# Nixie_Clock_Power_Supply.net
KiCad netlist of a schematic drawn in EasyEDA
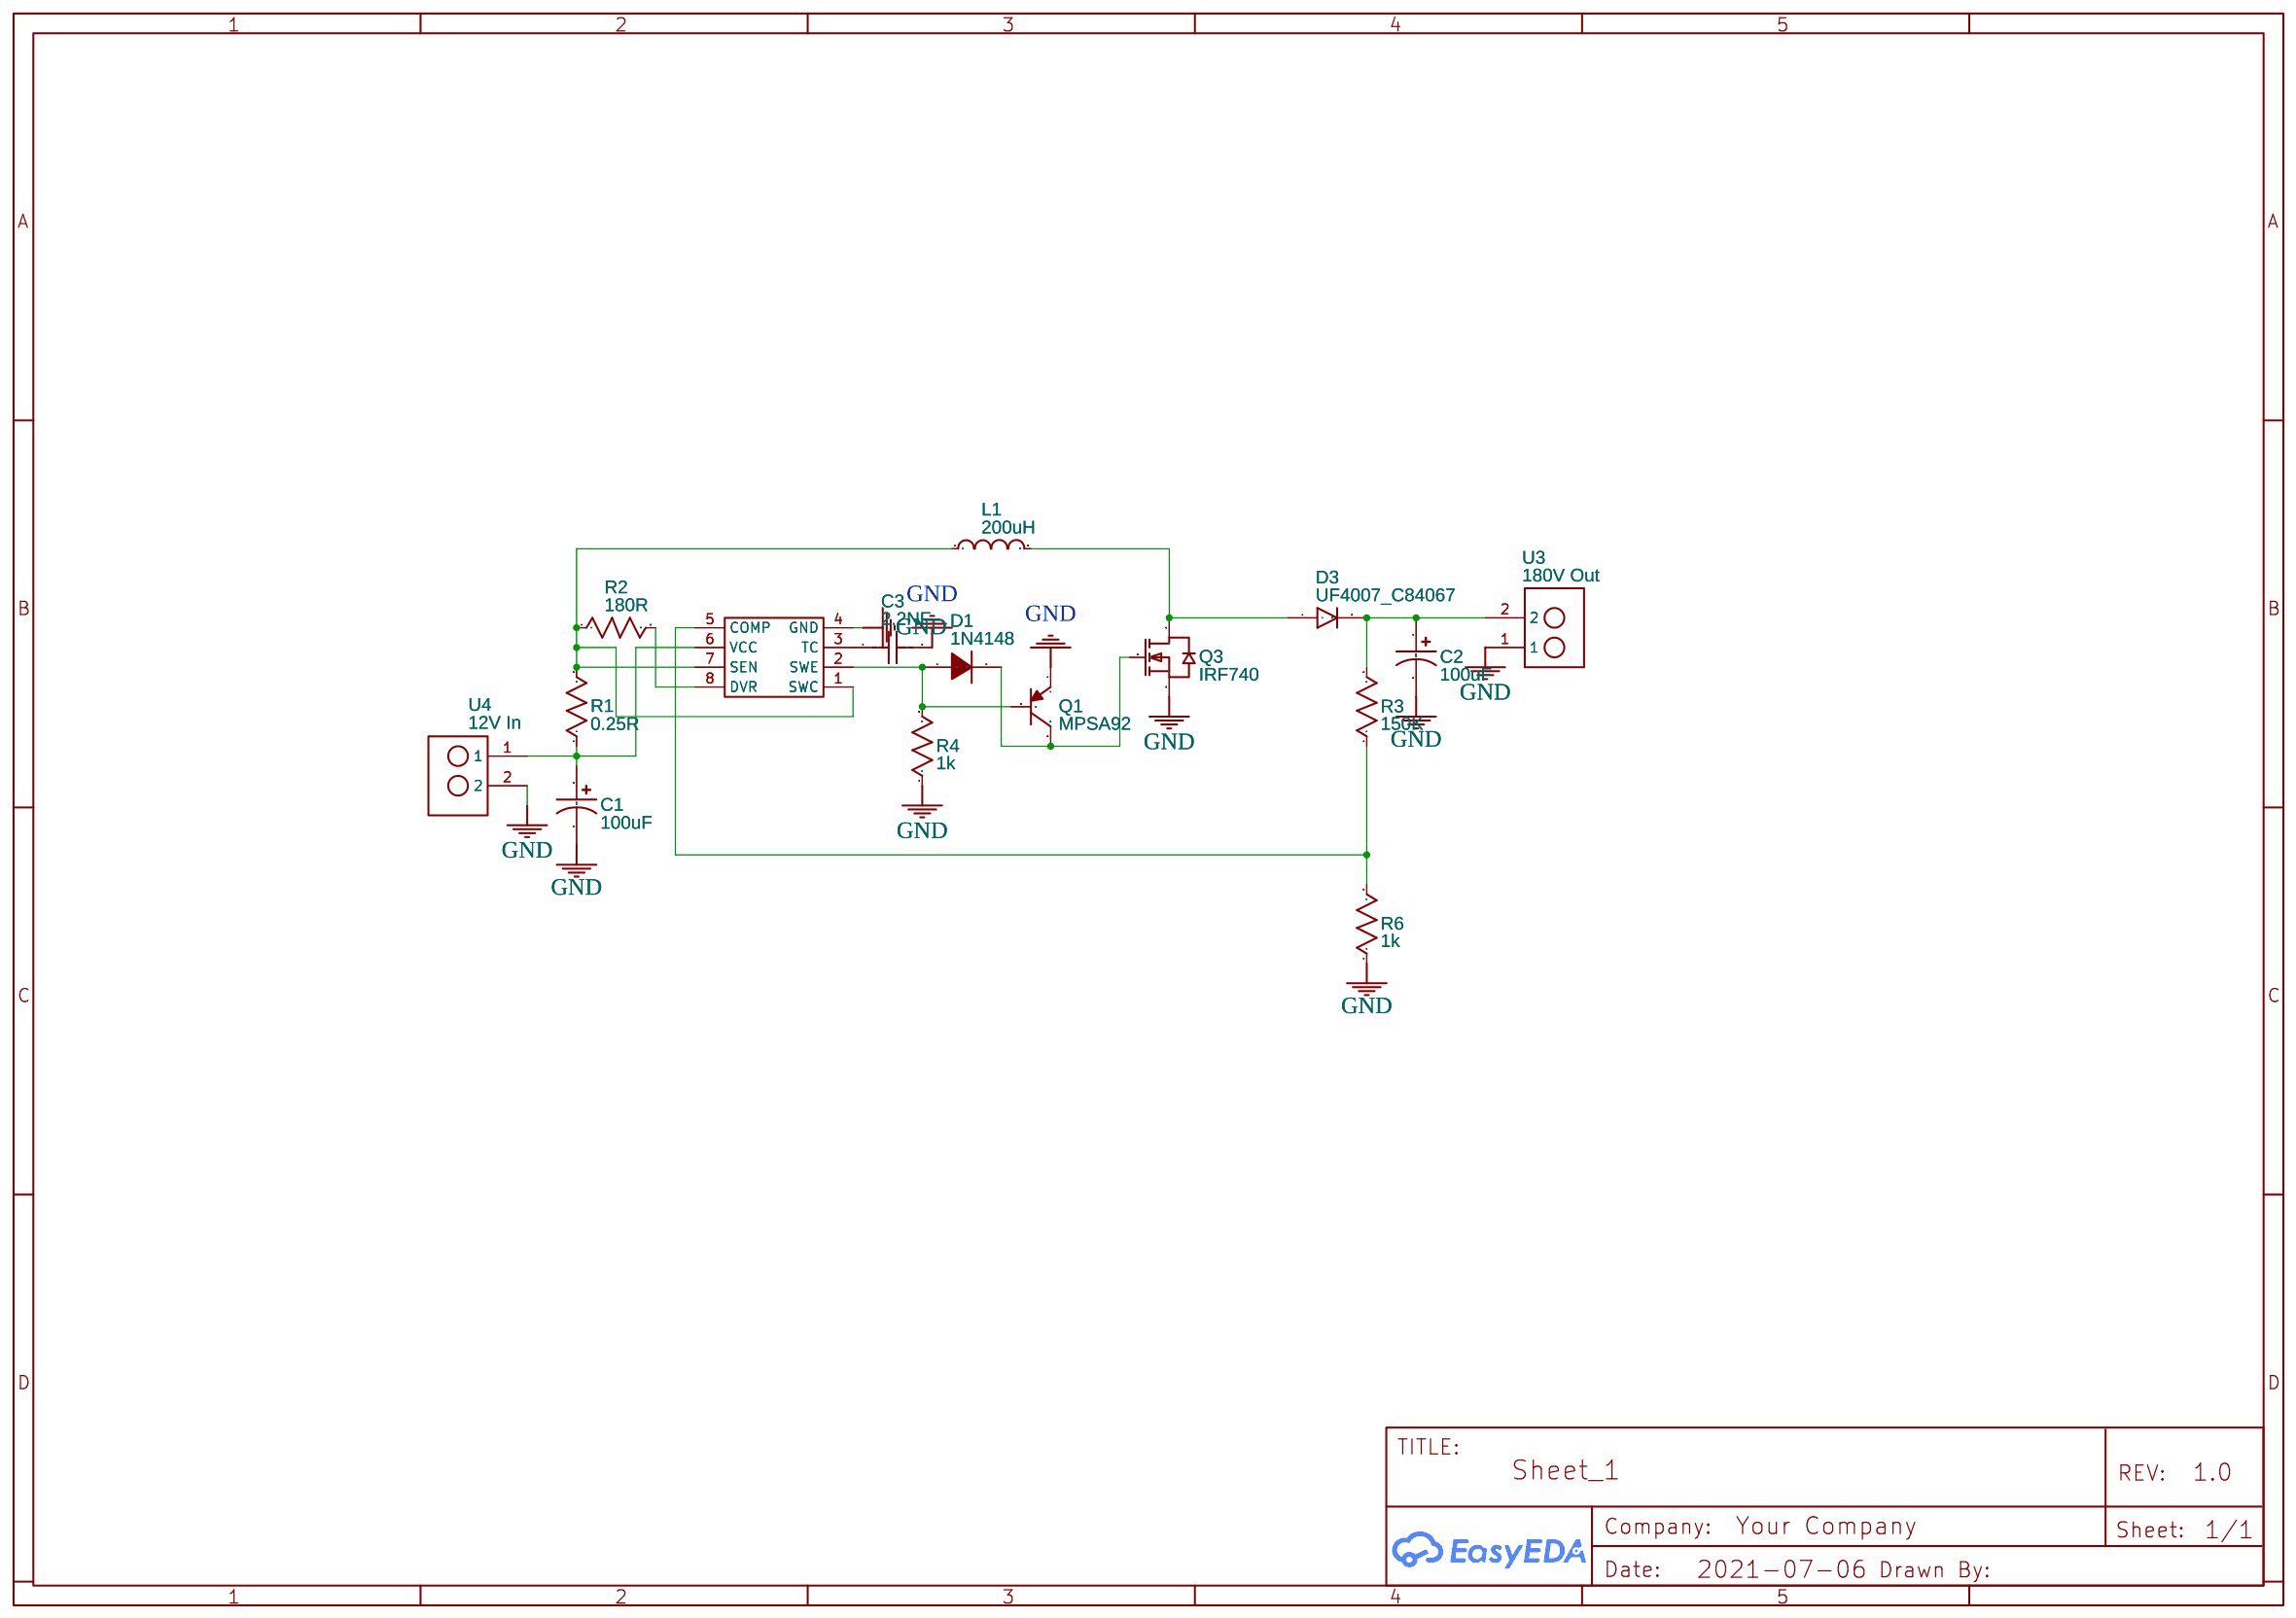
[diagram p0: schematic sheet]

(export (version "E")
  (design (tool "Eeschema 10.0.6"))
  (components
    (comp (ref "C1") (value "100uF") (libsource (lib "") (part "CE_TH_D5.0×F2.0_US")))
    (comp (ref "C2") (value "100uF") (libsource (lib "") (part "CE_TH_D12.5×F5.0_US")))
    (comp (ref "C3") (value "2.2NF") (libsource (lib "") (part "C_RAD-0.1_US")))
    (comp (ref "D1")
      (value "1N4148")
      (fields (field (name "BOM_Supplier Part") "C14516"))
      (libsource (lib "") (part "1N4148"))
    )
    (comp (ref "D3")
      (value "UF4007_C84067")
      (fields (field (name "BOM_Manufacturer Part") "UF4007") (field (name "BOM_Supplier Part") "C84067"))
      (libsource (lib "") (part "UF4007_C84067"))
    )
    (comp (ref "L1") (value "200uH") (libsource (lib "") (part "L_AXIAL-0.6_US")))
    (comp (ref "Q1")
      (value "MPSA92")
      (fields (field (name "BOM_Supplier Part") "C118558"))
      (libsource (lib "") (part "MPSA92"))
    )
    (comp (ref "Q3")
      (value "IRF740")
      (fields (field (name "BOM_Supplier Part") "C358408"))
      (libsource (lib "") (part "IRF740"))
    )
    (comp (ref "R1") (value "0.25R") (libsource (lib "") (part "R_AXIAL-0.4_US_1")))
    (comp (ref "R2") (value "180R") (libsource (lib "") (part "R_AXIAL-0.4_US")))
    (comp (ref "R3") (value "150K") (libsource (lib "") (part "R_AXIAL-0.4_US_1")))
    (comp (ref "R4") (value "1k") (libsource (lib "") (part "R_AXIAL-0.4_US_1")))
    (comp (ref "R6") (value "1k") (libsource (lib "") (part "R_AXIAL-0.4_US_1")))
    (comp (ref "U1")
      (value "MC34063AN")
      (fields (field (name "BOM_Supplier Part") "C126078"))
      (libsource (lib "") (part "MC34063AN"))
    )
    (comp (ref "U3") (value "180V Out") (libsource (lib "") (part "2 pin terminal_1")))
    (comp (ref "U4") (value "12V In") (libsource (lib "") (part "2 pin terminal")))
  )
  (nets
    (net (code "1") (name "GND") (class "Default")
      (node (ref "C1") (pin "2") (pinfunction "2_2") (pintype "unspecified"))
      (node (ref "C2") (pin "2") (pinfunction "2_2") (pintype "unspecified"))
      (node (ref "C3") (pin "2") (pinfunction "2_2") (pintype "unspecified"))
      (node (ref "Q1") (pin "1") (pinfunction "1_1") (pintype "input"))
      (node (ref "Q3") (pin "3") (pinfunction "S_3") (pintype "unspecified"))
      (node (ref "R4") (pin "1") (pinfunction "1_1") (pintype "unspecified"))
      (node (ref "R6") (pin "1") (pinfunction "1_1") (pintype "unspecified"))
      (node (ref "U1") (pin "4") (pinfunction "GND_4") (pintype "unspecified"))
      (node (ref "U3") (pin "1") (pinfunction "1_1") (pintype "unspecified"))
      (node (ref "U4") (pin "2") (pinfunction "2_2") (pintype "unspecified"))
    )
    (net (code "2") (name "Net-(D1-A)") (class "Default")
      (node (ref "D1") (pin "1") (pinfunction "A_1") (pintype "unspecified"))
      (node (ref "Q1") (pin "2") (pinfunction "2_2") (pintype "input"))
      (node (ref "R4") (pin "2") (pinfunction "2_2") (pintype "unspecified"))
      (node (ref "U1") (pin "2") (pinfunction "SWE_2") (pintype "unspecified"))
    )
    (net (code "3") (name "Net-(D1-C)") (class "Default")
      (node (ref "D1") (pin "2") (pinfunction "C_2") (pintype "unspecified"))
      (node (ref "Q1") (pin "3") (pinfunction "3_3") (pintype "input"))
      (node (ref "Q3") (pin "1") (pinfunction "G_1") (pintype "unspecified"))
    )
    (net (code "4") (name "Net-(D3-A)") (class "Default")
      (node (ref "D3") (pin "1") (pinfunction "A_1") (pintype "unspecified"))
      (node (ref "L1") (pin "2") (pinfunction "2_2") (pintype "unspecified"))
      (node (ref "Q3") (pin "2") (pinfunction "D_2") (pintype "unspecified"))
    )
    (net (code "5") (name "Net-(D3-C)") (class "Default")
      (node (ref "C2") (pin "1") (pinfunction "1_1") (pintype "unspecified"))
      (node (ref "D3") (pin "2") (pinfunction "C_2") (pintype "unspecified"))
      (node (ref "R3") (pin "2") (pinfunction "2_2") (pintype "unspecified"))
      (node (ref "U3") (pin "2") (pinfunction "2_2") (pintype "unspecified"))
    )
    (net (code "6") (name "Net-(U1-COMP)") (class "Default")
      (node (ref "R3") (pin "1") (pinfunction "1_1") (pintype "unspecified"))
      (node (ref "R6") (pin "2") (pinfunction "2_2") (pintype "unspecified"))
      (node (ref "U1") (pin "5") (pinfunction "COMP_5") (pintype "unspecified"))
    )
    (net (code "7") (name "Net-(U1-DVR)") (class "Default")
      (node (ref "R2") (pin "2") (pinfunction "2_2") (pintype "unspecified"))
      (node (ref "U1") (pin "8") (pinfunction "DVR_8") (pintype "unspecified"))
    )
    (net (code "8") (name "Net-(U1-SEN)") (class "Default")
      (node (ref "L1") (pin "1") (pinfunction "1_1") (pintype "unspecified"))
      (node (ref "R1") (pin "2") (pinfunction "2_2") (pintype "unspecified"))
      (node (ref "R2") (pin "1") (pinfunction "1_1") (pintype "unspecified"))
      (node (ref "U1") (pin "1") (pinfunction "SWC_1") (pintype "unspecified"))
      (node (ref "U1") (pin "7") (pinfunction "SEN_7") (pintype "unspecified"))
    )
    (net (code "9") (name "Net-(U1-TC)") (class "Default")
      (node (ref "C3") (pin "1") (pinfunction "1_1") (pintype "unspecified"))
      (node (ref "U1") (pin "3") (pinfunction "TC_3") (pintype "unspecified"))
    )
    (net (code "10") (name "Net-(U1-VCC)") (class "Default")
      (node (ref "C1") (pin "1") (pinfunction "1_1") (pintype "unspecified"))
      (node (ref "R1") (pin "1") (pinfunction "1_1") (pintype "unspecified"))
      (node (ref "U1") (pin "6") (pinfunction "VCC_6") (pintype "unspecified"))
      (node (ref "U4") (pin "1") (pinfunction "1_1") (pintype "unspecified"))
    )
  )
)
